# power.net
KiCad netlist of a schematic drawn in Altium Designer
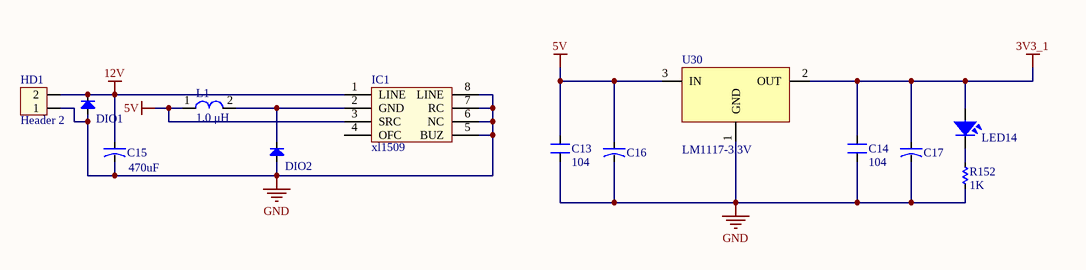
[diagram p0: power.SchDoc]

(export (version "E")
  (design (tool "Eeschema 10.0.6"))
  (components
    (comp (ref "C13")
      (value "104")
      (footprint "SM-CAP-0805")
      (fields (field (name "DESIGNED BY") "VanDungEvn"))
      (libsource (lib "electronicvn-library1") (part "CN"))
    )
    (comp (ref "C14")
      (value "104")
      (footprint "SM-CAP-0805")
      (fields (field (name "DESIGNED BY") "VanDungEvn"))
      (libsource (lib "electronicvn-library1") (part "CN"))
    )
    (comp (ref "C15")
      (value "470uF")
      (footprint "CAP-ALU-SMD-6.3x7.7x2.2")
      (description "Polarized Capacitor (Axial)")
      (fields (field (name "PUBLISHER") "Altium Limited"))
      (libsource (lib "LIBTanCN") (part "CN-ALU-SMD"))
    )
    (comp (ref "C16")
      (value "CN-ALU-SMD")
      (footprint "CAP-ALU-SMD-4.5x5x1.4")
      (description "Polarized Capacitor (Axial)")
      (fields (field (name "PUBLISHER") "Altium Limited"))
      (libsource (lib "LIBTanCN") (part "CN-ALU-SMD"))
    )
    (comp (ref "C17")
      (value "CN-ALU-SMD")
      (footprint "CAP-ALU-SMD-4.5x5x1.4")
      (description "Polarized Capacitor (Axial)")
      (fields (field (name "PUBLISHER") "Altium Limited"))
      (libsource (lib "LIBTanCN") (part "CN-ALU-SMD"))
    )
    (comp (ref "DIO1")
      (value "Diode SMD")
      (footprint "DIO-SMD-106")
      (description "Default Diode")
      (fields (field (name "PUBLISHER") "Altium Limited"))
      (libsource (lib "LIBRARY") (part "Diode SMD"))
    )
    (comp (ref "DIO2")
      (value "Diode SMD")
      (footprint "DIO-SMD-106")
      (description "Default Diode")
      (fields (field (name "PUBLISHER") "Altium Limited"))
      (libsource (lib "LIBRARY") (part "Diode SMD"))
    )
    (comp (ref "HD1")
      (value "Header 2")
      (footprint "HED2")
      (description "Header 2 (Green)")
      (libsource (lib "Tr.Thoai") (part "Hed2"))
    )
    (comp (ref "IC1")
      (value "xl1509")
      (footprint "SO-8")
      (description "Electronic Two-Tone Ringer")
      (libsource (lib "LIBTanCN") (part "LS1240A"))
    )
    (comp (ref "L1")
      (value "1.0 μH")
      (footprint "L-SMD-M-7.3x4.5")
      (fields
        (field (name "PARTNO") "78477010")
        (field (name "MANUFACTURER") "Wurth Elektronik")
        (field (name "CREATED BY") "Baojun Chen")
      )
      (libsource (lib "LIBRARY") (part "L-SMD-1"))
    )
    (comp (ref "LED14")
      (value "LED")
      (footprint "LED-0805-Blue")
      (libsource (lib "LIBRARY") (part "LED SMD"))
    )
    (comp (ref "R152")
      (value "1K")
      (footprint "RES-SMD-0805")
      (description "Resistor")
      (fields
        (field (name "MANUFACTURER") "Generic Components")
        (field (name "PUBLISHER") "Altium Hobart Technology Centre")
      )
      (libsource (lib "LIBRARY") (part "Res-SMD"))
    )
    (comp (ref "U30")
      (value "LM1117-3.3V")
      (footprint "SOT223")
      (description "800mA Low-Dropout Linear Regulator")
      (fields (field (name "CREATOR") "Nguyen Ba Bien"))
      (libsource (lib "LIBRARY") (part "LM1117"))
    )
  )
  (nets
    (net (code "1") (name "3V3_1") (class "Default")
      (node (ref "C14") (pin "2") (pinfunction "2_2") (pintype "passive"))
      (node (ref "C17") (pin "1") (pinfunction "1_1") (pintype "passive"))
      (node (ref "LED14") (pin "1") (pinfunction "1_1") (pintype "passive"))
      (node (ref "U30") (pin "2") (pinfunction "OUT_2") (pintype "passive"))
    )
    (net (code "2") (name "5V") (class "Default")
      (node (ref "C13") (pin "2") (pinfunction "2_2") (pintype "passive"))
      (node (ref "C16") (pin "1") (pinfunction "1_1") (pintype "passive"))
      (node (ref "IC1") (pin "3") (pinfunction "SRC_3") (pintype "passive"))
      (node (ref "L1") (pin "1") (pinfunction "1_1") (pintype "passive"))
      (node (ref "U30") (pin "3") (pinfunction "IN_3") (pintype "passive"))
    )
    (net (code "3") (name "12V") (class "Default")
      (node (ref "C15") (pin "1") (pinfunction "1_1") (pintype "passive"))
      (node (ref "DIO1") (pin "2") (pinfunction "K_2") (pintype "passive"))
      (node (ref "HD1") (pin "2") (pinfunction "2_2") (pintype "passive"))
      (node (ref "IC1") (pin "1") (pinfunction "LINE_1") (pintype "passive"))
    )
    (net (code "4") (name "GND") (class "Default")
      (node (ref "C13") (pin "1") (pinfunction "1_1") (pintype "passive"))
      (node (ref "C14") (pin "1") (pinfunction "1_1") (pintype "passive"))
      (node (ref "C15") (pin "2") (pinfunction "2_2") (pintype "passive"))
      (node (ref "C16") (pin "2") (pinfunction "2_2") (pintype "passive"))
      (node (ref "C17") (pin "2") (pinfunction "2_2") (pintype "passive"))
      (node (ref "DIO1") (pin "1") (pinfunction "A_1") (pintype "passive"))
      (node (ref "DIO2") (pin "1") (pinfunction "A_1") (pintype "passive"))
      (node (ref "HD1") (pin "1") (pinfunction "1_1") (pintype "passive"))
      (node (ref "IC1") (pin "5") (pinfunction "BUZ_5") (pintype "passive"))
      (node (ref "IC1") (pin "6") (pinfunction "NC_6") (pintype "passive"))
      (node (ref "IC1") (pin "7") (pinfunction "RC_7") (pintype "passive"))
      (node (ref "IC1") (pin "8") (pinfunction "LINE_8") (pintype "passive"))
      (node (ref "R152") (pin "2") (pinfunction "2_2") (pintype "passive"))
      (node (ref "U30") (pin "1") (pinfunction "GND_1") (pintype "passive"))
    )
    (net (code "5") (name "Net-(DIO2-K)") (class "Default")
      (node (ref "DIO2") (pin "2") (pinfunction "K_2") (pintype "passive"))
      (node (ref "IC1") (pin "2") (pinfunction "GND_2") (pintype "passive"))
      (node (ref "L1") (pin "2") (pinfunction "2_2") (pintype "passive"))
    )
    (net (code "6") (name "Net-(LED14-Pad2)") (class "Default")
      (node (ref "LED14") (pin "2") (pinfunction "2_2") (pintype "passive"))
      (node (ref "R152") (pin "1") (pinfunction "1_1") (pintype "passive"))
    )
    (net (code "7") (name "unconnected-(IC1-OFC-Pad4)") (class "Default")
      (node (ref "IC1") (pin "4") (pinfunction "OFC_4") (pintype "passive"))
    )
  )
)
